# M4QIDB-SCH-01_Sheet1.net
KiCad netlist of a schematic drawn in Altium Designer
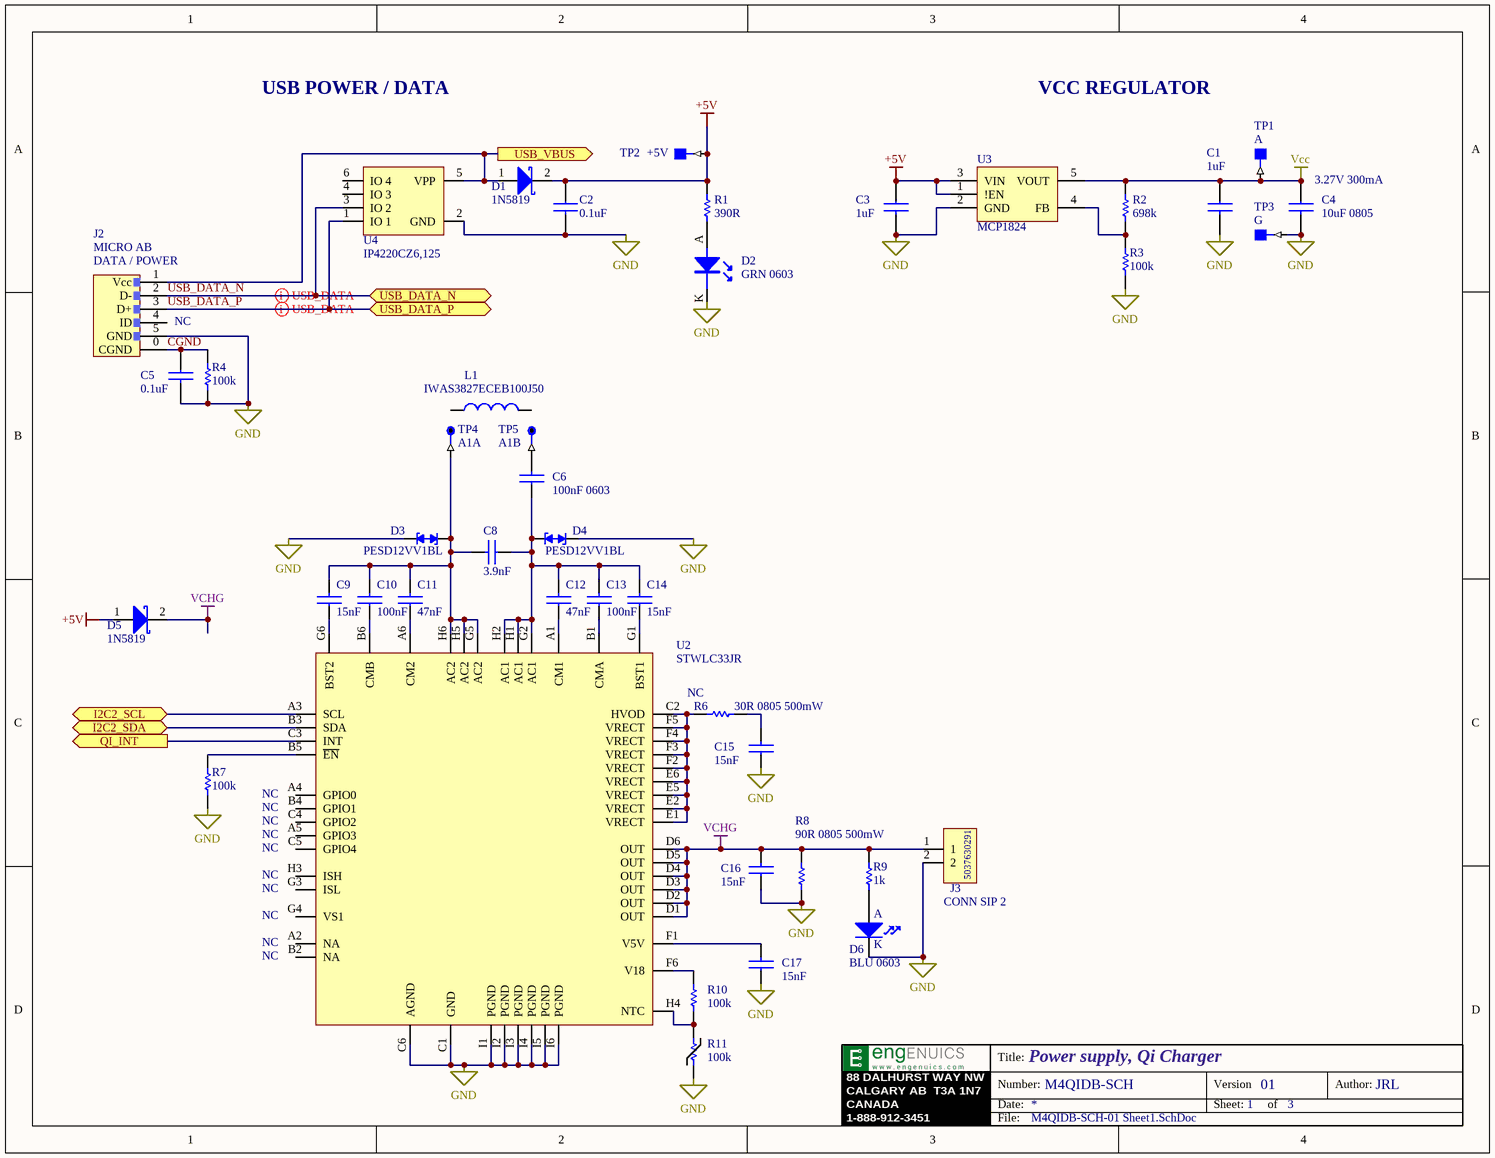
[diagram p0: M4QIDB-SCH-01 Sheet1.SchDoc]

(export (version "E")
  (design (tool "Eeschema 10.0.6"))
  (components
    (comp (ref "C1")
      (value "1uF")
      (footprint "0603 CAP3D")
      (fields
        (field (name "4. DIGI-KEY PART NUMBER") "587-1251-2-ND")
        (field (name "3. MANUFACTURER PART NUMBER") "EMK107BJ105KA-T")
        (field (name "5. INTERNAL PART NUMBER") "100009")
        (field (name "7. MODIFIED BY") "JRL")
      )
      (libsource (lib "PK Master Schematic Library") (part "CAPACITOR NON-POLARIZED"))
    )
    (comp (ref "C2")
      (value "0.1uF")
      (footprint "0603 CAP3D")
      (fields
        (field (name "4. DIGI-KEY PART NUMBER") "445-1316-2-ND")
        (field (name "3. MANUFACTURER PART NUMBER") "C1608X7R1E104K")
        (field (name "5. INTERNAL PART NUMBER") "100130")
        (field (name "7. MODIFIED BY") "JRL")
      )
      (libsource (lib "altium-import") (part "root_0_CAPACITOR NON-POLARIZED_"))
    )
    (comp (ref "C3")
      (value "1uF")
      (footprint "0603 CAP3D")
      (fields
        (field (name "4. DIGI-KEY PART NUMBER") "587-1251-2-ND")
        (field (name "3. MANUFACTURER PART NUMBER") "EMK107BJ105KA-T")
        (field (name "5. INTERNAL PART NUMBER") "100009")
        (field (name "7. MODIFIED BY") "JRL")
      )
      (libsource (lib "PK Master Schematic Library") (part "CAPACITOR NON-POLARIZED"))
    )
    (comp (ref "C4")
      (value "10uF 0805")
      (footprint "0805 CAP3D")
      (fields
        (field (name "4. DIGI-KEY PART NUMBER") "1276-1096-1-ND")
        (field (name "3. MANUFACTURER PART NUMBER") "CL21A106KOQNNNE")
        (field (name "5. INTERNAL PART NUMBER") "100006")
        (field (name "7. MODIFIED BY") "JRL")
      )
      (libsource (lib "PK Master Schematic Library") (part "CAPACITOR NON-POLARIZED"))
    )
    (comp (ref "C5")
      (value "0.1uF")
      (footprint "0603 CAP3D")
      (fields
        (field (name "4. DIGI-KEY PART NUMBER") "445-1316-2-ND")
        (field (name "3. MANUFACTURER PART NUMBER") "C1608X7R1E104K")
        (field (name "5. INTERNAL PART NUMBER") "100130")
        (field (name "7. MODIFIED BY") "JRL")
      )
      (libsource (lib "altium-import") (part "root_0_CAPACITOR NON-POLARIZED_"))
    )
    (comp (ref "C6")
      (value "100nF 0603")
      (footprint "0603 CAP3D")
      (fields
        (field (name "4. DIGI-KEY PART NUMBER") "311-1427-2-ND")
        (field (name "3. MANUFACTURER PART NUMBER") "CC0603KRX7R9BB473")
        (field (name "7. MODIFIED BY") "JRL")
      )
      (libsource (lib "Engenuics Master Schematic Library") (part "CAPACITOR NON-POLARIZED"))
    )
    (comp (ref "C8")
      (value "3.9nF")
      (footprint "0603 CAP3D")
      (fields
        (field (name "4. DIGI-KEY PART NUMBER") "490-1307-2-ND")
        (field (name "3. MANUFACTURER PART NUMBER") "CAP CER 3900PF 50V X7R 0402 NEED CROSS")
        (field (name "7. MODIFIED BY") "JRL")
      )
      (libsource (lib "Engenuics Master Schematic Library") (part "CAPACITOR NON-POLARIZED"))
    )
    (comp (ref "C9")
      (value "15nF")
      (footprint "0603 CAP3D")
      (fields
        (field (name "4. DIGI-KEY PART NUMBER") "399-3011-2-ND")
        (field (name "3. MANUFACTURER PART NUMBER") "C0402C153K8PACTU")
        (field (name "7. MODIFIED BY") "JRL")
      )
      (libsource (lib "Engenuics Master Schematic Library") (part "CAPACITOR NON-POLARIZED"))
    )
    (comp (ref "C10")
      (value "100nF")
      (footprint "0603 CAP3D")
      (fields
        (field (name "4. DIGI-KEY PART NUMBER") "490-10697-2-ND")
        (field (name "3. MANUFACTURER PART NUMBER") "GRM155R61H104KE14D")
        (field (name "7. MODIFIED BY") "JRL")
      )
      (libsource (lib "Engenuics Master Schematic Library") (part "CAPACITOR NON-POLARIZED"))
    )
    (comp (ref "C11")
      (value "47nF")
      (footprint "0603 CAP3D")
      (fields
        (field (name "4. DIGI-KEY PART NUMBER") "490-12705-2-ND")
        (field (name "3. MANUFACTURER PART NUMBER") "GRM155R61H473KE19 NEED CROSS")
        (field (name "7. MODIFIED BY") "JRL")
      )
      (libsource (lib "Engenuics Master Schematic Library") (part "CAPACITOR NON-POLARIZED"))
    )
    (comp (ref "C12")
      (value "47nF")
      (footprint "0603 CAP3D")
      (fields
        (field (name "4. DIGI-KEY PART NUMBER") "490-12705-2-ND")
        (field (name "3. MANUFACTURER PART NUMBER") "GRM155R61H473KE19 NEED CROSS")
        (field (name "7. MODIFIED BY") "JRL")
      )
      (libsource (lib "Engenuics Master Schematic Library") (part "CAPACITOR NON-POLARIZED"))
    )
    (comp (ref "C13")
      (value "100nF")
      (footprint "0603 CAP3D")
      (fields
        (field (name "4. DIGI-KEY PART NUMBER") "490-10697-2-ND")
        (field (name "3. MANUFACTURER PART NUMBER") "GRM155R61H104KE14D")
        (field (name "7. MODIFIED BY") "JRL")
      )
      (libsource (lib "Engenuics Master Schematic Library") (part "CAPACITOR NON-POLARIZED"))
    )
    (comp (ref "C14")
      (value "15nF")
      (footprint "0603 CAP3D")
      (fields
        (field (name "4. DIGI-KEY PART NUMBER") "399-3011-2-ND")
        (field (name "3. MANUFACTURER PART NUMBER") "C0402C153K8PACTU")
        (field (name "7. MODIFIED BY") "JRL")
      )
      (libsource (lib "Engenuics Master Schematic Library") (part "CAPACITOR NON-POLARIZED"))
    )
    (comp (ref "C15")
      (value "15nF")
      (footprint "0603 CAP3D")
      (fields
        (field (name "4. DIGI-KEY PART NUMBER") "399-3011-2-ND")
        (field (name "3. MANUFACTURER PART NUMBER") "C0402C153K8PACTU")
        (field (name "7. MODIFIED BY") "JRL")
      )
      (libsource (lib "Engenuics Master Schematic Library") (part "CAPACITOR NON-POLARIZED"))
    )
    (comp (ref "C16")
      (value "15nF")
      (footprint "0603 CAP3D")
      (fields
        (field (name "4. DIGI-KEY PART NUMBER") "399-3011-2-ND")
        (field (name "3. MANUFACTURER PART NUMBER") "C0402C153K8PACTU")
        (field (name "7. MODIFIED BY") "JRL")
      )
      (libsource (lib "Engenuics Master Schematic Library") (part "CAPACITOR NON-POLARIZED"))
    )
    (comp (ref "C17")
      (value "15nF")
      (footprint "0603 CAP3D")
      (fields
        (field (name "4. DIGI-KEY PART NUMBER") "399-3011-2-ND")
        (field (name "3. MANUFACTURER PART NUMBER") "C0402C153K8PACTU")
        (field (name "7. MODIFIED BY") "JRL")
      )
      (libsource (lib "Engenuics Master Schematic Library") (part "CAPACITOR NON-POLARIZED"))
    )
    (comp (ref "D1")
      (value "1N5819")
      (footprint "SOD123")
      (fields
        (field (name "3. MANUFACTURER PART NUMBER") "1N5819HW-7-F")
        (field (name "4. DIGI-KEY PART NUMBER") "1N5819HW-FDITR-ND")
        (field (name "5. INTERNAL PART NUMBER") "100039")
        (field (name "7. MODIFIED BY") "JRL")
      )
      (libsource (lib "Engenuics Master Schematic Library") (part "DIODE SCHOTTKY"))
    )
    (comp (ref "D2")
      (value "GRN 0603")
      (footprint "0603 AK")
      (description "LED")
      (fields
        (field (name "3. MANUFACTURER PART NUMBER") "APT1608SGC")
        (field (name "4. DIGI-KEY PART NUMBER") "754-1121-2-ND")
        (field (name "7. MODIFIED BY") "JRL")
      )
      (libsource (lib "altium-import") (part "root_3_LED T1-3/4_"))
    )
    (comp (ref "D3")
      (value "PESD12VV1BL")
      (footprint "SOD882")
      (fields
        (field (name "3. MANUFACTURER PART NUMBER") "PESD12VV1BL,315")
        (field (name "4. DIGI-KEY PART NUMBER") "1727-1304-2-ND")
        (field (name "7. MODIFIED BY") "JRL")
      )
      (libsource (lib "Engenuics Master Schematic Library") (part "DIODE ESD PESD12VVBL"))
    )
    (comp (ref "D4")
      (value "PESD12VV1BL")
      (footprint "SOD882")
      (fields
        (field (name "3. MANUFACTURER PART NUMBER") "PESD12VV1BL,315")
        (field (name "4. DIGI-KEY PART NUMBER") "1727-1304-2-ND")
        (field (name "7. MODIFIED BY") "JRL")
      )
      (libsource (lib "Engenuics Master Schematic Library") (part "DIODE ESD PESD12VVBL"))
    )
    (comp (ref "D5")
      (value "1N5819")
      (footprint "SOD123")
      (fields
        (field (name "3. MANUFACTURER PART NUMBER") "1N5819HW-7-F")
        (field (name "4. DIGI-KEY PART NUMBER") "1N5819HW-FDITR-ND")
        (field (name "5. INTERNAL PART NUMBER") "100039")
        (field (name "7. MODIFIED BY") "JRL")
      )
      (libsource (lib "Engenuics Master Schematic Library") (part "DIODE SCHOTTKY"))
    )
    (comp (ref "D6")
      (value "BLU 0603")
      (footprint "0603 AK")
      (fields
        (field (name "3. MANUFACTURER PART NUMBER") "APT1608QBC/D")
        (field (name "4. DIGI-KEY PART NUMBER") "754-1434-1-ND")
        (field (name "5. INTERNAL PART NUMBER") "100107")
        (field (name "7. MODIFIED BY") "JRL")
      )
      (libsource (lib "Engenuics Master Schematic Library") (part "LED AK"))
    )
    (comp (ref "J2")
      (value "MICRO AB")
      (footprint "CONN USB MICRO B SMT LEGS FCI 10118193")
      (fields
        (field (name "3. MANUFACTURER PART NUMBER") "10104111-0001LF")
        (field (name "4. DIGI-KEY PART NUMBER") "609-4053-1-ND")
        (field (name "5. INTERNAL PART NUMBER") "100182")
        (field (name "7. MODIFIED BY") "JRL")
      )
      (libsource (lib "Engenuics Master Schematic Library") (part "CONN USB MICRO AB FCI 10104111"))
    )
    (comp (ref "J3")
      (value "CONN SIP 2")
      (footprint "HDR1X2")
      (fields
        (field (name "3. MANUFACTURER PART NUMBER") "5037630291")
        (field (name "4. DIGI-KEY PART NUMBER") "WM10654TR-ND")
        (field (name "7. MODIFIED BY") "JRL")
      )
      (libsource (lib "Engenuics Master Schematic Library") (part "CONN 2POS MOLEX 5037630291"))
    )
    (comp (ref "L1")
      (value "IWAS3827ECEB100J50")
      (footprint "HDR1X2 NP")
      (fields (field (name "7. MODIFIED BY") "*"))
      (libsource (lib "Engenuics Master Schematic Library") (part "INDUCTOR"))
    )
    (comp (ref "R1")
      (value "390R")
      (footprint "0603")
      (fields
        (field (name "4. DIGI-KEY PART NUMBER") "311-390HRTR-ND")
        (field (name "3. MANUFACTURER PART NUMBER") "RC0603FR-07390RL")
        (field (name "5. INTERNAL PART NUMBER") "100098")
        (field (name "7. MODIFIED BY") "JRL")
      )
      (libsource (lib "Blackline Master Schematic Library") (part "RESISTOR"))
    )
    (comp (ref "R2")
      (value "698k")
      (footprint "0603")
      (fields
        (field (name "4. DIGI-KEY PART NUMBER") "311-698KHRCT-ND")
        (field (name "3. MANUFACTURER PART NUMBER") "RC0603FR-07698KL")
        (field (name "7. MODIFIED BY") "JRL")
      )
      (libsource (lib "PK Master Schematic Library") (part "RESISTOR"))
    )
    (comp (ref "R3")
      (value "100k")
      (footprint "0603")
      (fields
        (field (name "4. DIGI-KEY PART NUMBER") "311-100KHRTR-ND")
        (field (name "3. MANUFACTURER PART NUMBER") "RC0603FR-07100KL")
        (field (name "5. INTERNAL PART NUMBER") "100078")
        (field (name "7. MODIFIED BY") "JRL")
      )
      (libsource (lib "altium-import") (part "root_3_RESISTOR_"))
    )
    (comp (ref "R4")
      (value "100k")
      (footprint "0603")
      (fields
        (field (name "4. DIGI-KEY PART NUMBER") "311-100KHRTR-ND")
        (field (name "3. MANUFACTURER PART NUMBER") "RC0603FR-07100KL")
        (field (name "5. INTERNAL PART NUMBER") "100078")
        (field (name "7. MODIFIED BY") "JRL")
      )
      (libsource (lib "altium-import") (part "root_1_RESISTOR_"))
    )
    (comp (ref "R6")
      (value "30R 0805 500mW")
      (footprint "0805")
      (fields
        (field (name "4. DIGI-KEY PART NUMBER") "ERJ-P6WF30R0V-ND")
        (field (name "3. MANUFACTURER PART NUMBER") "ERJ-P6WF30R0V")
        (field (name "7. MODIFIED BY") "JRL")
      )
      (libsource (lib "") (part "RESISTOR_1"))
    )
    (comp (ref "R7")
      (value "100k")
      (footprint "0603")
      (fields (field (name "7. MODIFIED BY") "*"))
      (libsource (lib "Engenuics Master Schematic Library") (part "RESISTOR"))
    )
    (comp (ref "R8")
      (value "90R 0805 500mW")
      (footprint "0805")
      (fields
        (field (name "4. DIGI-KEY PART NUMBER") "ERJ-P6WF30R0V-ND")
        (field (name "3. MANUFACTURER PART NUMBER") "ERJ-P6WF30R0V")
        (field (name "7. MODIFIED BY") "JRL")
      )
      (libsource (lib "Engenuics Master Schematic Library") (part "RESISTOR"))
    )
    (comp (ref "R9")
      (value "1k")
      (footprint "0603")
      (fields (field (name "7. MODIFIED BY") "*"))
      (libsource (lib "Engenuics Master Schematic Library") (part "RESISTOR"))
    )
    (comp (ref "R10")
      (value "100k")
      (footprint "0603")
      (fields (field (name "7. MODIFIED BY") "*"))
      (libsource (lib "Engenuics Master Schematic Library") (part "RESISTOR"))
    )
    (comp (ref "R11")
      (value "100k")
      (footprint "0603")
      (fields (field (name "7. MODIFIED BY") "*"))
      (libsource (lib "Engenuics Master Schematic Library") (part "RESISTOR"))
    )
    (comp (ref "TP1")
      (value "A")
      (footprint "TEST POINT SMT")
      (fields (field (name "7. MODIFIED BY") "JRL"))
      (libsource (lib "PK Master Schematic Library") (part "TEST POINT SMT"))
    )
    (comp (ref "TP2")
      (value "+5V")
      (footprint "TEST POINT SMT")
      (fields (field (name "7. MODIFIED BY") "JRL"))
      (libsource (lib "Blackline Master Schematic Library") (part "TEST POINT SMT"))
    )
    (comp (ref "TP3")
      (value "G")
      (footprint "TEST POINT SMT")
      (fields (field (name "7. MODIFIED BY") "JRL"))
      (libsource (lib "PK Master Schematic Library") (part "TEST POINT SMT"))
    )
    (comp (ref "TP4")
      (value "A1A")
      (footprint "TEST POINT THRU HOLE")
      (fields (field (name "7. MODIFIED BY") "JRL"))
      (libsource (lib "Engenuics Master Schematic Library") (part "TEST POINT THRU HOLE"))
    )
    (comp (ref "TP5")
      (value "A1B")
      (footprint "TEST POINT THRU HOLE")
      (fields (field (name "7. MODIFIED BY") "JRL"))
      (libsource (lib "Engenuics Master Schematic Library") (part "TEST POINT THRU HOLE"))
    )
    (comp (ref "U2")
      (value "STWLC33JR")
      (footprint "FLIP CHIP 3.97x2.67mm")
      (fields (field (name "4. DIGI-KEY PART NUMBER") "497-17649-2-ND") (field (name "7. MODIFIED BY") "JRL"))
      (libsource (lib "Engenuics Master Schematic Library") (part "IC WIRESLESS CHARGER STWLC33JR"))
    )
    (comp (ref "U3")
      (value "MCP1824")
      (footprint "SOT23-5")
      (fields
        (field (name "3. MANUFACTURER PART NUMBER") "MCP1824T-ADJE/OT")
        (field (name "4. DIGI-KEY PART NUMBER") "MCP1824T-ADJE/OTCT-ND")
        (field (name "7. MODIFIED BY") "JRL")
      )
      (libsource (lib "PK Master Schematic Library") (part "VREG MCP1824"))
    )
    (comp (ref "U4")
      (value "IP4220CZ6,125")
      (footprint "TSOP95P280X110-6N")
      (fields
        (field (name "4. DIGI-KEY PART NUMBER") "568-3529-6-ND")
        (field (name "5. INTERNAL PART NUMBER") "100225")
        (field (name "7. MODIFIED BY") "JRL")
      )
      (libsource (lib "Engenuics Master Schematic Library") (part "IC ESD USB DUAL NXP IP4220CZ6"))
    )
  )
  (nets
    (net (code "1") (name "+5V") (class "Default")
      (node (ref "C2") (pin "1") (pinfunction "1_1") (pintype "passive"))
      (node (ref "C3") (pin "1") (pinfunction "1_1") (pintype "passive"))
      (node (ref "D1") (pin "2") (pinfunction "2_2") (pintype "passive"))
      (node (ref "D5") (pin "1") (pinfunction "1_1") (pintype "passive"))
      (node (ref "R1") (pin "2") (pinfunction "2_2") (pintype "passive"))
      (node (ref "TP2") (pin "1") (pinfunction "1_1") (pintype "input"))
      (node (ref "U3") (pin "1") (pinfunction "!EN_1") (pintype "passive"))
      (node (ref "U3") (pin "3") (pinfunction "VIN_3") (pintype "passive"))
    )
    (net (code "2") (name "/CGND") (class "Default")
      (node (ref "C5") (pin "1") (pinfunction "1_1") (pintype "passive"))
      (node (ref "J2") (pin "0") (pinfunction "CGND_0") (pintype "passive"))
      (node (ref "R4") (pin "2") (pinfunction "2_2") (pintype "passive"))
    )
    (net (code "3") (name "/I2C2_SCL") (class "Default")
      (node (ref "U2") (pin "A3") (pinfunction "SCL_A3") (pintype "passive"))
    )
    (net (code "4") (name "/I2C2_SDA") (class "Default")
      (node (ref "U2") (pin "B3") (pinfunction "SDA_B3") (pintype "passive"))
    )
    (net (code "5") (name "/QI_INT") (class "Default")
      (node (ref "U2") (pin "C3") (pinfunction "INT_C3") (pintype "passive"))
    )
    (net (code "6") (name "/USB_DATA_N") (class "Default")
      (node (ref "J2") (pin "2") (pinfunction "D-_2") (pintype "passive"))
      (node (ref "U4") (pin "3") (pinfunction "IO_2_3") (pintype "passive"))
    )
    (net (code "7") (name "/USB_DATA_P") (class "Default")
      (node (ref "J2") (pin "3") (pinfunction "D+_3") (pintype "passive"))
      (node (ref "U4") (pin "1") (pinfunction "IO_1_1") (pintype "passive"))
    )
    (net (code "8") (name "/USB_VBUS") (class "Default")
      (node (ref "D1") (pin "1") (pinfunction "1_1") (pintype "passive"))
      (node (ref "J2") (pin "1") (pinfunction "Vcc_1") (pintype "passive"))
      (node (ref "U4") (pin "5") (pinfunction "VPP_5") (pintype "passive"))
    )
    (net (code "9") (name "GND") (class "Default")
      (node (ref "C1") (pin "2") (pinfunction "2_2") (pintype "passive"))
      (node (ref "C15") (pin "1") (pinfunction "1_1") (pintype "passive"))
      (node (ref "C16") (pin "1") (pinfunction "1_1") (pintype "passive"))
      (node (ref "C17") (pin "1") (pinfunction "1_1") (pintype "passive"))
      (node (ref "C2") (pin "2") (pinfunction "2_2") (pintype "passive"))
      (node (ref "C3") (pin "2") (pinfunction "2_2") (pintype "passive"))
      (node (ref "C4") (pin "2") (pinfunction "2_2") (pintype "passive"))
      (node (ref "C5") (pin "2") (pinfunction "2_2") (pintype "passive"))
      (node (ref "D2") (pin "K") (pinfunction "K1_K") (pintype "passive"))
      (node (ref "D3") (pin "2") (pinfunction "2_2") (pintype "passive"))
      (node (ref "D4") (pin "2") (pinfunction "2_2") (pintype "passive"))
      (node (ref "D6") (pin "K") (pinfunction "K_K") (pintype "passive"))
      (node (ref "J2") (pin "5") (pinfunction "GND_5") (pintype "passive"))
      (node (ref "J3") (pin "2") (pinfunction "2_2") (pintype "passive"))
      (node (ref "R11") (pin "2") (pinfunction "2_2") (pintype "passive"))
      (node (ref "R3") (pin "2") (pinfunction "2_2") (pintype "passive"))
      (node (ref "R4") (pin "1") (pinfunction "1_1") (pintype "passive"))
      (node (ref "R7") (pin "2") (pinfunction "2_2") (pintype "passive"))
      (node (ref "R8") (pin "2") (pinfunction "2_2") (pintype "passive"))
      (node (ref "TP3") (pin "1") (pinfunction "1_1") (pintype "input"))
      (node (ref "U2") (pin "C1") (pinfunction "GND_C1") (pintype "passive"))
      (node (ref "U2") (pin "C6") (pinfunction "AGND_C6") (pintype "passive"))
      (node (ref "U2") (pin "I1") (pinfunction "PGND_I1") (pintype "passive"))
      (node (ref "U2") (pin "I2") (pinfunction "PGND_I2") (pintype "passive"))
      (node (ref "U2") (pin "I3") (pinfunction "PGND_I3") (pintype "passive"))
      (node (ref "U2") (pin "I4") (pinfunction "PGND_I4") (pintype "passive"))
      (node (ref "U2") (pin "I5") (pinfunction "PGND_I5") (pintype "passive"))
      (node (ref "U2") (pin "I6") (pinfunction "PGND_I6") (pintype "passive"))
      (node (ref "U3") (pin "2") (pinfunction "GND_2") (pintype "passive"))
      (node (ref "U4") (pin "2") (pinfunction "GND_2") (pintype "passive"))
    )
    (net (code "10") (name "Net-(C6-Pad2)") (class "Default")
      (node (ref "C6") (pin "2") (pinfunction "2_2") (pintype "passive"))
      (node (ref "TP5") (pin "1") (pinfunction "1_1") (pintype "input"))
    )
    (net (code "11") (name "Net-(C10-Pad2)") (class "Default")
      (node (ref "C10") (pin "2") (pinfunction "2_2") (pintype "passive"))
      (node (ref "C11") (pin "2") (pinfunction "2_2") (pintype "passive"))
      (node (ref "C8") (pin "2") (pinfunction "2_2") (pintype "passive"))
      (node (ref "C9") (pin "2") (pinfunction "2_2") (pintype "passive"))
      (node (ref "D3") (pin "1") (pinfunction "1_1") (pintype "passive"))
      (node (ref "TP4") (pin "1") (pinfunction "1_1") (pintype "input"))
      (node (ref "U2") (pin "G5") (pinfunction "AC2_G5") (pintype "passive"))
      (node (ref "U2") (pin "H5") (pinfunction "AC2_H5") (pintype "passive"))
      (node (ref "U2") (pin "H6") (pinfunction "AC2_H6") (pintype "passive"))
    )
    (net (code "12") (name "Net-(C12-Pad2)") (class "Default")
      (node (ref "C12") (pin "2") (pinfunction "2_2") (pintype "passive"))
      (node (ref "C13") (pin "2") (pinfunction "2_2") (pintype "passive"))
      (node (ref "C14") (pin "2") (pinfunction "2_2") (pintype "passive"))
      (node (ref "C6") (pin "1") (pinfunction "1_1") (pintype "passive"))
      (node (ref "C8") (pin "1") (pinfunction "1_1") (pintype "passive"))
      (node (ref "D4") (pin "1") (pinfunction "1_1") (pintype "passive"))
      (node (ref "U2") (pin "G2") (pinfunction "AC1_G2") (pintype "passive"))
      (node (ref "U2") (pin "H1") (pinfunction "AC1_H1") (pintype "passive"))
      (node (ref "U2") (pin "H2") (pinfunction "AC1_H2") (pintype "passive"))
    )
    (net (code "13") (name "Net-(C15-Pad2)") (class "Default")
      (node (ref "C15") (pin "2") (pinfunction "2_2") (pintype "passive"))
      (node (ref "R6") (pin "2") (pinfunction "2_2") (pintype "passive"))
    )
    (net (code "14") (name "Net-(D2-A1)") (class "Default")
      (node (ref "D2") (pin "A") (pinfunction "A1_A") (pintype "passive"))
      (node (ref "R1") (pin "1") (pinfunction "1_1") (pintype "passive"))
    )
    (net (code "15") (name "Net-(D6-PadA)") (class "Default")
      (node (ref "D6") (pin "A") (pinfunction "A_A") (pintype "passive"))
      (node (ref "R9") (pin "2") (pinfunction "2_2") (pintype "passive"))
    )
    (net (code "16") (name "Net-(U2-BST1)") (class "Default")
      (node (ref "C14") (pin "1") (pinfunction "1_1") (pintype "passive"))
      (node (ref "U2") (pin "G1") (pinfunction "BST1_G1") (pintype "passive"))
    )
    (net (code "17") (name "Net-(U2-BST2)") (class "Default")
      (node (ref "C9") (pin "1") (pinfunction "1_1") (pintype "passive"))
      (node (ref "U2") (pin "G6") (pinfunction "BST2_G6") (pintype "passive"))
    )
    (net (code "18") (name "Net-(U2-CM1)") (class "Default")
      (node (ref "C12") (pin "1") (pinfunction "1_1") (pintype "passive"))
      (node (ref "U2") (pin "A1") (pinfunction "CM1_A1") (pintype "passive"))
    )
    (net (code "19") (name "Net-(U2-CM2)") (class "Default")
      (node (ref "C11") (pin "1") (pinfunction "1_1") (pintype "passive"))
      (node (ref "U2") (pin "A6") (pinfunction "CM2_A6") (pintype "passive"))
    )
    (net (code "20") (name "Net-(U2-CMA)") (class "Default")
      (node (ref "C13") (pin "1") (pinfunction "1_1") (pintype "passive"))
      (node (ref "U2") (pin "B1") (pinfunction "CMA_B1") (pintype "passive"))
    )
    (net (code "21") (name "Net-(U2-CMB)") (class "Default")
      (node (ref "C10") (pin "1") (pinfunction "1_1") (pintype "passive"))
      (node (ref "U2") (pin "B6") (pinfunction "CMB_B6") (pintype "passive"))
    )
    (net (code "22") (name "Net-(U2-HVOD)") (class "Default")
      (node (ref "R6") (pin "1") (pinfunction "1_1") (pintype "passive"))
      (node (ref "U2") (pin "C2") (pinfunction "HVOD_C2") (pintype "passive"))
      (node (ref "U2") (pin "E1") (pinfunction "VRECT_E1") (pintype "passive"))
      (node (ref "U2") (pin "E2") (pinfunction "VRECT_E2") (pintype "passive"))
      (node (ref "U2") (pin "E5") (pinfunction "VRECT_E5") (pintype "passive"))
      (node (ref "U2") (pin "E6") (pinfunction "VRECT_E6") (pintype "passive"))
      (node (ref "U2") (pin "F2") (pinfunction "VRECT_F2") (pintype "passive"))
      (node (ref "U2") (pin "F3") (pinfunction "VRECT_F3") (pintype "passive"))
      (node (ref "U2") (pin "F4") (pinfunction "VRECT_F4") (pintype "passive"))
      (node (ref "U2") (pin "F5") (pinfunction "VRECT_F5") (pintype "passive"))
    )
    (net (code "23") (name "Net-(U2-NTC)") (class "Default")
      (node (ref "R10") (pin "2") (pinfunction "2_2") (pintype "passive"))
      (node (ref "R11") (pin "1") (pinfunction "1_1") (pintype "passive"))
      (node (ref "U2") (pin "H4") (pinfunction "NTC_H4") (pintype "passive"))
    )
    (net (code "24") (name "Net-(U2-V5V)") (class "Default")
      (node (ref "C17") (pin "2") (pinfunction "2_2") (pintype "passive"))
      (node (ref "U2") (pin "F1") (pinfunction "V5V_F1") (pintype "passive"))
    )
    (net (code "25") (name "Net-(U2-V18)") (class "Default")
      (node (ref "R10") (pin "1") (pinfunction "1_1") (pintype "passive"))
      (node (ref "U2") (pin "F6") (pinfunction "V18_F6") (pintype "passive"))
    )
    (net (code "26") (name "Net-(U2-~{EN})") (class "Default")
      (node (ref "R7") (pin "1") (pinfunction "1_1") (pintype "passive"))
      (node (ref "U2") (pin "B5") (pinfunction "~{EN}_B5") (pintype "passive"))
    )
    (net (code "27") (name "Net-(U3-FB)") (class "Default")
      (node (ref "R2") (pin "1") (pinfunction "1_1") (pintype "passive"))
      (node (ref "R3") (pin "1") (pinfunction "1_1") (pintype "passive"))
      (node (ref "U3") (pin "4") (pinfunction "FB_4") (pintype "passive"))
    )
    (net (code "28") (name "VCHG") (class "Default")
      (node (ref "C16") (pin "2") (pinfunction "2_2") (pintype "passive"))
      (node (ref "D5") (pin "2") (pinfunction "2_2") (pintype "passive"))
      (node (ref "J3") (pin "1") (pinfunction "1_1") (pintype "passive"))
      (node (ref "R8") (pin "1") (pinfunction "1_1") (pintype "passive"))
      (node (ref "R9") (pin "1") (pinfunction "1_1") (pintype "passive"))
      (node (ref "U2") (pin "D1") (pinfunction "OUT_D1") (pintype "passive"))
      (node (ref "U2") (pin "D2") (pinfunction "OUT_D2") (pintype "passive"))
      (node (ref "U2") (pin "D3") (pinfunction "OUT_D3") (pintype "passive"))
      (node (ref "U2") (pin "D4") (pinfunction "OUT_D4") (pintype "passive"))
      (node (ref "U2") (pin "D5") (pinfunction "OUT_D5") (pintype "passive"))
      (node (ref "U2") (pin "D6") (pinfunction "OUT_D6") (pintype "passive"))
    )
    (net (code "29") (name "Vcc") (class "Default")
      (node (ref "C1") (pin "1") (pinfunction "1_1") (pintype "passive"))
      (node (ref "C4") (pin "1") (pinfunction "1_1") (pintype "passive"))
      (node (ref "R2") (pin "2") (pinfunction "2_2") (pintype "passive"))
      (node (ref "TP1") (pin "1") (pinfunction "1_1") (pintype "input"))
      (node (ref "U3") (pin "5") (pinfunction "VOUT_5") (pintype "passive"))
    )
    (net (code "30") (name "unconnected-(J2-ID-Pad4)") (class "Default")
      (node (ref "J2") (pin "4") (pinfunction "ID_4") (pintype "passive"))
    )
    (net (code "31") (name "unconnected-(L1-Pad1)") (class "Default")
      (node (ref "L1") (pin "1") (pinfunction "1_1") (pintype "passive"))
    )
    (net (code "32") (name "unconnected-(L1-Pad2)") (class "Default")
      (node (ref "L1") (pin "2") (pinfunction "2_2") (pintype "passive"))
    )
    (net (code "33") (name "unconnected-(U2-GPIO0-PadA4)") (class "Default")
      (node (ref "U2") (pin "A4") (pinfunction "GPIO0_A4") (pintype "passive"))
    )
    (net (code "34") (name "unconnected-(U2-GPIO1-PadB4)") (class "Default")
      (node (ref "U2") (pin "B4") (pinfunction "GPIO1_B4") (pintype "passive"))
    )
    (net (code "35") (name "unconnected-(U2-GPIO2-PadC4)") (class "Default")
      (node (ref "U2") (pin "C4") (pinfunction "GPIO2_C4") (pintype "passive"))
    )
    (net (code "36") (name "unconnected-(U2-GPIO3-PadA5)") (class "Default")
      (node (ref "U2") (pin "A5") (pinfunction "GPIO3_A5") (pintype "passive"))
    )
    (net (code "37") (name "unconnected-(U2-GPIO4-PadC5)") (class "Default")
      (node (ref "U2") (pin "C5") (pinfunction "GPIO4_C5") (pintype "passive"))
    )
    (net (code "38") (name "unconnected-(U2-ISH-PadH3)") (class "Default")
      (node (ref "U2") (pin "H3") (pinfunction "ISH_H3") (pintype "passive"))
    )
    (net (code "39") (name "unconnected-(U2-ISL-PadG3)") (class "Default")
      (node (ref "U2") (pin "G3") (pinfunction "ISL_G3") (pintype "passive"))
    )
    (net (code "40") (name "unconnected-(U2-NA-PadA2)") (class "Default")
      (node (ref "U2") (pin "A2") (pinfunction "NA_A2") (pintype "passive"))
    )
    (net (code "41") (name "unconnected-(U2-NA-PadB2)") (class "Default")
      (node (ref "U2") (pin "B2") (pinfunction "NA_B2") (pintype "passive"))
    )
    (net (code "42") (name "unconnected-(U2-VS1-PadG4)") (class "Default")
      (node (ref "U2") (pin "G4") (pinfunction "VS1_G4") (pintype "passive"))
    )
    (net (code "43") (name "unconnected-(U4-IO_3-Pad4)") (class "Default")
      (node (ref "U4") (pin "4") (pinfunction "IO_3_4") (pintype "passive"))
    )
    (net (code "44") (name "unconnected-(U4-IO_4-Pad6)") (class "Default")
      (node (ref "U4") (pin "6") (pinfunction "IO_4_6") (pintype "passive"))
    )
  )
)
